# version1.net
KiCad netlist of a schematic drawn in EAGLE
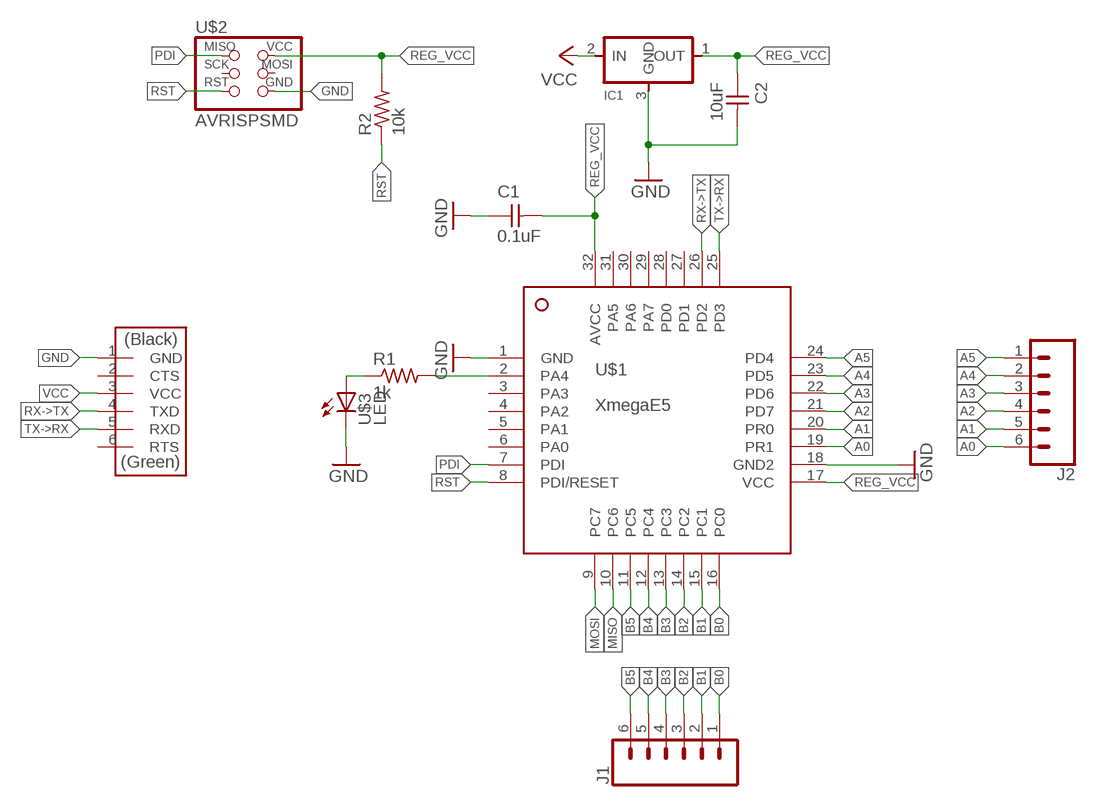
[diagram p0: schematic, sheet 1]

(export (version "E")
  (design (tool "Eeschema 10.0.6"))
  (components
    (comp (ref "C1")
      (value "0.1uF")
      (footprint "eagle-import:C1206FAB")
      (libsource (lib "eagle-import") (part "CAP-UNPOLARIZEDFAB"))
    )
    (comp (ref "C2")
      (value "10uF")
      (footprint "eagle-import:C1206FAB")
      (libsource (lib "eagle-import") (part "CAP-UNPOLARIZEDFAB"))
    )
    (comp (ref "IC1")
      (value "REGULATORSOT23")
      (footprint "eagle-import:SOT23")
      (libsource (lib "eagle-import") (part "REGULATORSOT23"))
    )
    (comp (ref "J1")
      (value "CONN_06SMD_MALE")
      (footprint "eagle-import:1X06_SMD_MALE")
      (libsource (lib "eagle-import") (part "CONN_06SMD_MALE"))
    )
    (comp (ref "J2")
      (value "CONN_06SMD_MALE")
      (footprint "eagle-import:1X06_SMD_MALE")
      (libsource (lib "eagle-import") (part "CONN_06SMD_MALE"))
    )
    (comp (ref "R1")
      (value "1k")
      (footprint "eagle-import:R1206FAB")
      (libsource (lib "eagle-import") (part "RES-US1206FAB"))
    )
    (comp (ref "R2")
      (value "10k")
      (footprint "eagle-import:R1206FAB")
      (libsource (lib "eagle-import") (part "RES-US1206FAB"))
    )
    (comp (ref "U$1")
      (value "XmegaE5")
      (footprint "eagle-import:QFP80P900X900X120-32N")
      (libsource (lib "eagle-import") (part "ATXMEGA8E5-M4UTQFP"))
    )
    (comp (ref "U$2")
      (value "AVRISPSMD")
      (footprint "eagle-import:2X03SMD")
      (libsource (lib "eagle-import") (part "AVRISPSMD"))
    )
    (comp (ref "U$3")
      (value "LED")
      (footprint "eagle-import:LED1206FAB")
      (libsource (lib "eagle-import") (part "LEDFAB1206"))
    )
    (comp (ref "U$4")
      (value "FTDI-SMD-HEADER")
      (footprint "eagle-import:1X06SMD")
      (libsource (lib "eagle-import") (part "FTDI-SMD-HEADER"))
    )
  )
  (nets
    (net (code "1") (name "A0") (class "Default")
      (node (ref "J2") (pin "6") (pinfunction "6_6") (pintype "passive"))
      (node (ref "U$1") (pin "19") (pinfunction "PR1_19") (pintype "bidirectional"))
    )
    (net (code "2") (name "A1") (class "Default")
      (node (ref "J2") (pin "5") (pinfunction "5_5") (pintype "passive"))
      (node (ref "U$1") (pin "20") (pinfunction "PR0_20") (pintype "bidirectional"))
    )
    (net (code "3") (name "A2") (class "Default")
      (node (ref "J2") (pin "4") (pinfunction "4_4") (pintype "passive"))
      (node (ref "U$1") (pin "21") (pinfunction "PD7_21") (pintype "bidirectional"))
    )
    (net (code "4") (name "A3") (class "Default")
      (node (ref "J2") (pin "3") (pinfunction "3_3") (pintype "passive"))
      (node (ref "U$1") (pin "22") (pinfunction "PD6_22") (pintype "bidirectional"))
    )
    (net (code "5") (name "A4") (class "Default")
      (node (ref "J2") (pin "2") (pinfunction "2_2") (pintype "passive"))
      (node (ref "U$1") (pin "23") (pinfunction "PD5_23") (pintype "bidirectional"))
    )
    (net (code "6") (name "A5") (class "Default")
      (node (ref "J2") (pin "1") (pinfunction "1_1") (pintype "passive"))
      (node (ref "U$1") (pin "24") (pinfunction "PD4_24") (pintype "bidirectional"))
    )
    (net (code "7") (name "B0") (class "Default")
      (node (ref "J1") (pin "1") (pinfunction "1_1") (pintype "passive"))
      (node (ref "U$1") (pin "16") (pinfunction "PC0_16") (pintype "bidirectional"))
    )
    (net (code "8") (name "B1") (class "Default")
      (node (ref "J1") (pin "2") (pinfunction "2_2") (pintype "passive"))
      (node (ref "U$1") (pin "15") (pinfunction "PC1_15") (pintype "bidirectional"))
    )
    (net (code "9") (name "B2") (class "Default")
      (node (ref "J1") (pin "3") (pinfunction "3_3") (pintype "passive"))
      (node (ref "U$1") (pin "14") (pinfunction "PC2_14") (pintype "bidirectional"))
    )
    (net (code "10") (name "B3") (class "Default")
      (node (ref "J1") (pin "4") (pinfunction "4_4") (pintype "passive"))
      (node (ref "U$1") (pin "13") (pinfunction "PC3_13") (pintype "bidirectional"))
    )
    (net (code "11") (name "B4") (class "Default")
      (node (ref "J1") (pin "5") (pinfunction "5_5") (pintype "passive"))
      (node (ref "U$1") (pin "12") (pinfunction "PC4_12") (pintype "bidirectional"))
    )
    (net (code "12") (name "B5") (class "Default")
      (node (ref "J1") (pin "6") (pinfunction "6_6") (pintype "passive"))
      (node (ref "U$1") (pin "11") (pinfunction "PC5_11") (pintype "bidirectional"))
    )
    (net (code "13") (name "GND") (class "Default")
      (node (ref "C1") (pin "1") (pinfunction "1_1") (pintype "passive"))
      (node (ref "C2") (pin "2") (pinfunction "2_2") (pintype "passive"))
      (node (ref "IC1") (pin "3") (pinfunction "GND_3") (pintype "bidirectional"))
      (node (ref "U$1") (pin "1") (pinfunction "GND_1") (pintype "passive"))
      (node (ref "U$1") (pin "18") (pinfunction "GND2_18") (pintype "passive"))
      (node (ref "U$2") (pin "6") (pinfunction "GND_6") (pintype "passive"))
      (node (ref "U$3") (pin "2") (pinfunction "C_2") (pintype "passive"))
      (node (ref "U$4") (pin "1") (pinfunction "GND_1") (pintype "bidirectional"))
    )
    (net (code "14") (name "MISO") (class "Default")
      (node (ref "U$1") (pin "10") (pinfunction "PC6_10") (pintype "bidirectional"))
    )
    (net (code "15") (name "MOSI") (class "Default")
      (node (ref "U$1") (pin "9") (pinfunction "PC7_9") (pintype "bidirectional"))
    )
    (net (code "16") (name "Net-(U$1-PA4)") (class "Default")
      (node (ref "R1") (pin "2") (pinfunction "2_2") (pintype "passive"))
      (node (ref "U$1") (pin "2") (pinfunction "PA4_2") (pintype "bidirectional"))
    )
    (net (code "17") (name "Net-(U$3-A)") (class "Default")
      (node (ref "R1") (pin "1") (pinfunction "1_1") (pintype "passive"))
      (node (ref "U$3") (pin "1") (pinfunction "A_1") (pintype "passive"))
    )
    (net (code "18") (name "PDI") (class "Default")
      (node (ref "U$1") (pin "7") (pinfunction "PDI_7") (pintype "input"))
      (node (ref "U$2") (pin "1") (pinfunction "MISO_1") (pintype "passive"))
    )
    (net (code "19") (name "REG_VCC") (class "Default")
      (node (ref "C1") (pin "2") (pinfunction "2_2") (pintype "passive"))
      (node (ref "C2") (pin "1") (pinfunction "1_1") (pintype "passive"))
      (node (ref "IC1") (pin "1") (pinfunction "OUT_1") (pintype "bidirectional"))
      (node (ref "R2") (pin "2") (pinfunction "2_2") (pintype "passive"))
      (node (ref "U$1") (pin "17") (pinfunction "VCC_17") (pintype "power_in"))
      (node (ref "U$1") (pin "32") (pinfunction "AVCC_32") (pintype "power_in"))
      (node (ref "U$2") (pin "2") (pinfunction "VCC_2") (pintype "passive"))
    )
    (net (code "20") (name "RST") (class "Default")
      (node (ref "R2") (pin "1") (pinfunction "1_1") (pintype "passive"))
      (node (ref "U$1") (pin "8") (pinfunction "PDI/RESET_8") (pintype "input"))
      (node (ref "U$2") (pin "5") (pinfunction "RST_5") (pintype "passive"))
    )
    (net (code "21") (name "RX->TX") (class "Default")
      (node (ref "U$1") (pin "26") (pinfunction "PD2_26") (pintype "bidirectional"))
      (node (ref "U$4") (pin "4") (pinfunction "TXD_4") (pintype "bidirectional"))
    )
    (net (code "22") (name "TX->RX") (class "Default")
      (node (ref "U$1") (pin "25") (pinfunction "PD3_25") (pintype "bidirectional"))
      (node (ref "U$4") (pin "5") (pinfunction "RXD_5") (pintype "bidirectional"))
    )
    (net (code "23") (name "VCC") (class "Default")
      (node (ref "IC1") (pin "2") (pinfunction "IN_2") (pintype "bidirectional"))
      (node (ref "U$4") (pin "3") (pinfunction "VCC_3") (pintype "bidirectional"))
    )
    (net (code "24") (name "unconnected-(U$1-PA0-Pad6)") (class "Default")
      (node (ref "U$1") (pin "6") (pinfunction "PA0_6") (pintype "bidirectional"))
    )
    (net (code "25") (name "unconnected-(U$1-PA1-Pad5)") (class "Default")
      (node (ref "U$1") (pin "5") (pinfunction "PA1_5") (pintype "bidirectional"))
    )
    (net (code "26") (name "unconnected-(U$1-PA2-Pad4)") (class "Default")
      (node (ref "U$1") (pin "4") (pinfunction "PA2_4") (pintype "bidirectional"))
    )
    (net (code "27") (name "unconnected-(U$1-PA3-Pad3)") (class "Default")
      (node (ref "U$1") (pin "3") (pinfunction "PA3_3") (pintype "bidirectional"))
    )
    (net (code "28") (name "unconnected-(U$1-PA5-Pad31)") (class "Default")
      (node (ref "U$1") (pin "31") (pinfunction "PA5_31") (pintype "bidirectional"))
    )
    (net (code "29") (name "unconnected-(U$1-PA6-Pad30)") (class "Default")
      (node (ref "U$1") (pin "30") (pinfunction "PA6_30") (pintype "bidirectional"))
    )
    (net (code "30") (name "unconnected-(U$1-PA7-Pad29)") (class "Default")
      (node (ref "U$1") (pin "29") (pinfunction "PA7_29") (pintype "bidirectional"))
    )
    (net (code "31") (name "unconnected-(U$1-PD0-Pad28)") (class "Default")
      (node (ref "U$1") (pin "28") (pinfunction "PD0_28") (pintype "bidirectional"))
    )
    (net (code "32") (name "unconnected-(U$1-PD1-Pad27)") (class "Default")
      (node (ref "U$1") (pin "27") (pinfunction "PD1_27") (pintype "bidirectional"))
    )
    (net (code "33") (name "unconnected-(U$2-MOSI-Pad4)") (class "Default")
      (node (ref "U$2") (pin "4") (pinfunction "MOSI_4") (pintype "passive"))
    )
    (net (code "34") (name "unconnected-(U$2-SCK-Pad3)") (class "Default")
      (node (ref "U$2") (pin "3") (pinfunction "SCK_3") (pintype "passive"))
    )
    (net (code "35") (name "unconnected-(U$4-CTS-Pad2)") (class "Default")
      (node (ref "U$4") (pin "2") (pinfunction "CTS_2") (pintype "bidirectional"))
    )
    (net (code "36") (name "unconnected-(U$4-RTS-Pad6)") (class "Default")
      (node (ref "U$4") (pin "6") (pinfunction "RTS_6") (pintype "bidirectional"))
    )
  )
)
